# Test_2019.net
KiCad netlist of a schematic drawn in EAGLE
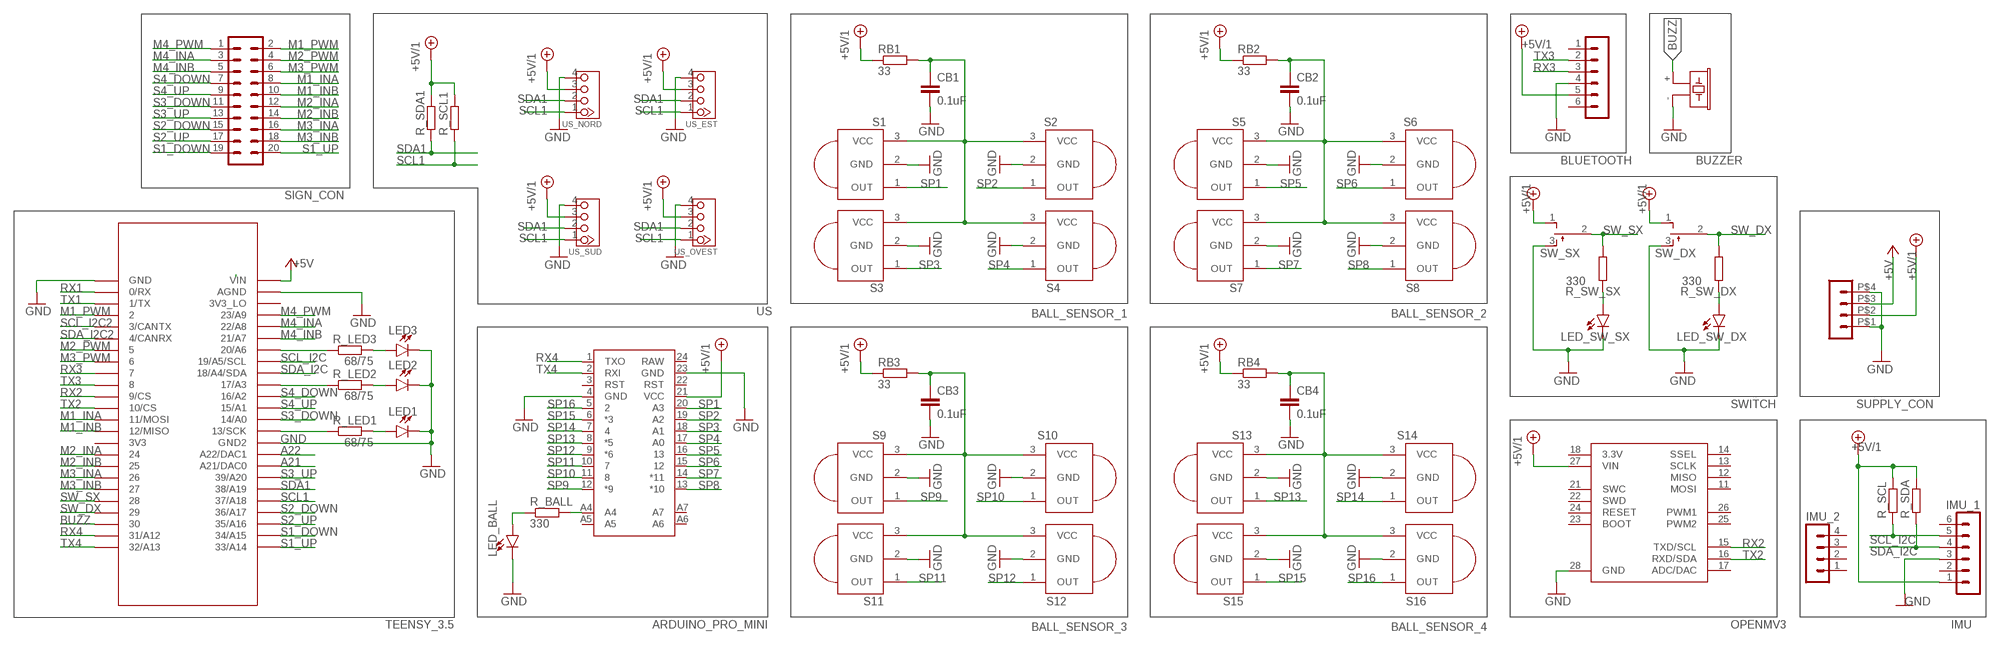
[diagram p0: schematic, sheet 1]

(export (version "E")
  (design (tool "Eeschema 10.0.6"))
  (components
    (comp (ref "ARDUINO_PRO_MINI")
      (value "ARDUINO_PRO_MINI")
      (footprint "eagle-import:ARDUINO_PRO_MINI")
      (libsource (lib "eagle-import") (part "ARDUINO_PRO_MINI"))
    )
    (comp (ref "BLUETOOTH")
      (value "MA06-1")
      (footprint "eagle-import:MA06-1")
      (libsource (lib "eagle-import") (part "MA06-1"))
    )
    (comp (ref "BUZZER")
      (value "F/CM12P")
      (footprint "eagle-import:F_CM12P")
      (libsource (lib "eagle-import") (part "F/CM12P"))
    )
    (comp (ref "CB1")
      (value "0.1uF")
      (footprint "eagle-import:C1206")
      (libsource (lib "eagle-import") (part "C-EUC1206"))
    )
    (comp (ref "CB2")
      (value "0.1uF")
      (footprint "eagle-import:C1206")
      (libsource (lib "eagle-import") (part "C-EUC1206"))
    )
    (comp (ref "CB3")
      (value "0.1uF")
      (footprint "eagle-import:C1206")
      (libsource (lib "eagle-import") (part "C-EUC1206"))
    )
    (comp (ref "CB4")
      (value "0.1uF")
      (footprint "eagle-import:C1206")
      (libsource (lib "eagle-import") (part "C-EUC1206"))
    )
    (comp (ref "IMU_1")
      (value "MA06-1")
      (footprint "eagle-import:MA06-1")
      (libsource (lib "eagle-import") (part "MA06-1"))
    )
    (comp (ref "IMU_2")
      (value "MA04-1")
      (footprint "eagle-import:MA04-1")
      (libsource (lib "eagle-import") (part "MA04-1"))
    )
    (comp (ref "LED1")
      (value "LED3MM")
      (footprint "eagle-import:LED_3MM")
      (libsource (lib "eagle-import") (part "LED3MM"))
    )
    (comp (ref "LED2")
      (value "LED3MM")
      (footprint "eagle-import:LED_3MM")
      (libsource (lib "eagle-import") (part "LED3MM"))
    )
    (comp (ref "LED3")
      (value "LED3MM")
      (footprint "eagle-import:LED_3MM")
      (libsource (lib "eagle-import") (part "LED3MM"))
    )
    (comp (ref "LED_BALL")
      (value "LED3MM")
      (footprint "eagle-import:LED_3MM")
      (libsource (lib "eagle-import") (part "LED3MM"))
    )
    (comp (ref "LED_SW_DX")
      (value "LED3MM")
      (footprint "eagle-import:LED_3MM")
      (libsource (lib "eagle-import") (part "LED3MM"))
    )
    (comp (ref "LED_SW_SX")
      (value "LED3MM")
      (footprint "eagle-import:LED_3MM")
      (libsource (lib "eagle-import") (part "LED3MM"))
    )
    (comp (ref "RB1")
      (value "33")
      (footprint "eagle-import:R0805")
      (libsource (lib "eagle-import") (part "R-EU_R0805"))
    )
    (comp (ref "RB2")
      (value "33")
      (footprint "eagle-import:R0805")
      (libsource (lib "eagle-import") (part "R-EU_R0805"))
    )
    (comp (ref "RB3")
      (value "33")
      (footprint "eagle-import:R0805")
      (libsource (lib "eagle-import") (part "R-EU_R0805"))
    )
    (comp (ref "RB4")
      (value "33")
      (footprint "eagle-import:R0805")
      (libsource (lib "eagle-import") (part "R-EU_R0805"))
    )
    (comp (ref "R_BALL")
      (value "330")
      (footprint "eagle-import:R1206")
      (libsource (lib "eagle-import") (part "R-EU_R1206"))
    )
    (comp (ref "R_LED1")
      (value "68/75")
      (footprint "eagle-import:R0805")
      (libsource (lib "eagle-import") (part "R-EU_R0805"))
    )
    (comp (ref "R_LED2")
      (value "68/75")
      (footprint "eagle-import:R0805")
      (libsource (lib "eagle-import") (part "R-EU_R0805"))
    )
    (comp (ref "R_LED3")
      (value "68/75")
      (footprint "eagle-import:R0805")
      (libsource (lib "eagle-import") (part "R-EU_R0805"))
    )
    (comp (ref "R_SCL")
      (value "3.3k")
      (footprint "eagle-import:R0805")
      (libsource (lib "eagle-import") (part "R-EU_R0805"))
    )
    (comp (ref "R_SCL1")
      (value "3.3k")
      (footprint "eagle-import:R0805")
      (libsource (lib "eagle-import") (part "R-EU_R0805"))
    )
    (comp (ref "R_SDA")
      (value "3.3k")
      (footprint "eagle-import:R0805")
      (libsource (lib "eagle-import") (part "R-EU_R0805"))
    )
    (comp (ref "R_SDA1")
      (value "3.3k")
      (footprint "eagle-import:R0805")
      (libsource (lib "eagle-import") (part "R-EU_R0805"))
    )
    (comp (ref "R_SW_DX")
      (value "330")
      (footprint "eagle-import:R0805")
      (libsource (lib "eagle-import") (part "R-EU_R0805"))
    )
    (comp (ref "R_SW_SX")
      (value "330")
      (footprint "eagle-import:R0805")
      (libsource (lib "eagle-import") (part "R-EU_R0805"))
    )
    (comp (ref "S1")
      (value "PNA460XM")
      (footprint "eagle-import:PNA460XM")
      (libsource (lib "eagle-import") (part "PNA460XM"))
    )
    (comp (ref "S2")
      (value "PNA460XM")
      (footprint "eagle-import:PNA460XM")
      (libsource (lib "eagle-import") (part "PNA460XM"))
    )
    (comp (ref "S3")
      (value "PNA460XM")
      (footprint "eagle-import:PNA460XM")
      (libsource (lib "eagle-import") (part "PNA460XM"))
    )
    (comp (ref "S4")
      (value "PNA460XM")
      (footprint "eagle-import:PNA460XM")
      (libsource (lib "eagle-import") (part "PNA460XM"))
    )
    (comp (ref "S5")
      (value "PNA460XM")
      (footprint "eagle-import:PNA460XM")
      (libsource (lib "eagle-import") (part "PNA460XM"))
    )
    (comp (ref "S6")
      (value "PNA460XM")
      (footprint "eagle-import:PNA460XM")
      (libsource (lib "eagle-import") (part "PNA460XM"))
    )
    (comp (ref "S7")
      (value "PNA460XM")
      (footprint "eagle-import:PNA460XM")
      (libsource (lib "eagle-import") (part "PNA460XM"))
    )
    (comp (ref "S8")
      (value "PNA460XM")
      (footprint "eagle-import:PNA460XM")
      (libsource (lib "eagle-import") (part "PNA460XM"))
    )
    (comp (ref "S9")
      (value "PNA460XM")
      (footprint "eagle-import:PNA460XM")
      (libsource (lib "eagle-import") (part "PNA460XM"))
    )
    (comp (ref "S10")
      (value "PNA460XM")
      (footprint "eagle-import:PNA460XM")
      (libsource (lib "eagle-import") (part "PNA460XM"))
    )
    (comp (ref "S11")
      (value "PNA460XM")
      (footprint "eagle-import:PNA460XM")
      (libsource (lib "eagle-import") (part "PNA460XM"))
    )
    (comp (ref "S12")
      (value "PNA460XM")
      (footprint "eagle-import:PNA460XM")
      (libsource (lib "eagle-import") (part "PNA460XM"))
    )
    (comp (ref "S13")
      (value "PNA460XM")
      (footprint "eagle-import:PNA460XM")
      (libsource (lib "eagle-import") (part "PNA460XM"))
    )
    (comp (ref "S14")
      (value "PNA460XM")
      (footprint "eagle-import:PNA460XM")
      (libsource (lib "eagle-import") (part "PNA460XM"))
    )
    (comp (ref "S15")
      (value "PNA460XM")
      (footprint "eagle-import:PNA460XM")
      (libsource (lib "eagle-import") (part "PNA460XM"))
    )
    (comp (ref "S16")
      (value "PNA460XM")
      (footprint "eagle-import:PNA460XM")
      (libsource (lib "eagle-import") (part "PNA460XM"))
    )
    (comp (ref "SIGN_CON")
      (value "20V")
      (footprint "eagle-import:20V")
      (libsource (lib "eagle-import") (part "20V"))
    )
    (comp (ref "SUPPLY_CON")
      (value "HEADER_POS4_43045-0412")
      (footprint "eagle-import:43045-0412")
      (libsource (lib "eagle-import") (part "HEADER_POS4_?43045-0412"))
    )
    (comp (ref "SW_DX")
      (value "TL38PO")
      (footprint "eagle-import:TL3XPO")
      (libsource (lib "eagle-import") (part "TL38PO"))
    )
    (comp (ref "SW_SX")
      (value "TL38PO")
      (footprint "eagle-import:TL3XPO")
      (libsource (lib "eagle-import") (part "TL38PO"))
    )
    (comp (ref "TEENSY_3.5")
      (value "TEENSY_3.5/3.6")
      (footprint "eagle-import:TEENSY_3.5_3.6")
      (libsource (lib "eagle-import") (part "TEENSY_3.5/3.6"))
    )
    (comp (ref "U$2")
      (value "OPENMV3")
      (footprint "eagle-import:OPENMV3")
      (libsource (lib "eagle-import") (part "OPENMV3"))
    )
    (comp (ref "US_EST")
      (value "TWIG_2.0")
      (footprint "eagle-import:2.0_1X4")
      (libsource (lib "eagle-import") (part "TWIG_2.0"))
    )
    (comp (ref "US_NORD")
      (value "TWIG_2.0")
      (footprint "eagle-import:2.0_1X4")
      (libsource (lib "eagle-import") (part "TWIG_2.0"))
    )
    (comp (ref "US_OVEST")
      (value "TWIG_2.0")
      (footprint "eagle-import:2.0_1X4")
      (libsource (lib "eagle-import") (part "TWIG_2.0"))
    )
    (comp (ref "US_SUD")
      (value "TWIG_2.0")
      (footprint "eagle-import:2.0_1X4")
      (libsource (lib "eagle-import") (part "TWIG_2.0"))
    )
  )
  (nets
    (net (code "1") (name "+5V") (class "Default")
      (node (ref "SUPPLY_CON") (pin "P$3") (pinfunction "3_P$3") (pintype "passive"))
      (node (ref "TEENSY_3.5") (pin "VIN") (pinfunction "VIN_VIN") (pintype "bidirectional"))
    )
    (net (code "2") (name "+5V{slash}1") (class "Default")
      (node (ref "ARDUINO_PRO_MINI") (pin "21") (pinfunction "VCC_21") (pintype "power_in"))
      (node (ref "BLUETOOTH") (pin "5") (pinfunction "5_5") (pintype "passive"))
      (node (ref "IMU_1") (pin "1") (pinfunction "1_1") (pintype "passive"))
      (node (ref "RB1") (pin "1") (pinfunction "1_1") (pintype "passive"))
      (node (ref "RB2") (pin "1") (pinfunction "1_1") (pintype "passive"))
      (node (ref "RB3") (pin "1") (pinfunction "1_1") (pintype "passive"))
      (node (ref "RB4") (pin "1") (pinfunction "1_1") (pintype "passive"))
      (node (ref "R_SCL") (pin "2") (pinfunction "2_2") (pintype "passive"))
      (node (ref "R_SCL1") (pin "2") (pinfunction "2_2") (pintype "passive"))
      (node (ref "R_SDA") (pin "2") (pinfunction "2_2") (pintype "passive"))
      (node (ref "R_SDA1") (pin "2") (pinfunction "2_2") (pintype "passive"))
      (node (ref "SUPPLY_CON") (pin "P$2") (pinfunction "2_P$2") (pintype "passive"))
      (node (ref "SW_DX") (pin "1") (pinfunction "O_1") (pintype "passive"))
      (node (ref "SW_SX") (pin "1") (pinfunction "O_1") (pintype "passive"))
      (node (ref "U$2") (pin "27") (pinfunction "VIN_27") (pintype "power_in"))
      (node (ref "US_EST") (pin "3") (pinfunction "3_3") (pintype "bidirectional"))
      (node (ref "US_NORD") (pin "3") (pinfunction "3_3") (pintype "bidirectional"))
      (node (ref "US_OVEST") (pin "3") (pinfunction "3_3") (pintype "bidirectional"))
      (node (ref "US_SUD") (pin "3") (pinfunction "3_3") (pintype "bidirectional"))
    )
    (net (code "3") (name "/3.3V") (class "Default")
      (node (ref "U$2") (pin "18") (pinfunction "3.3V_18") (pintype "power_in"))
    )
    (net (code "4") (name "/A21") (class "Default")
      (node (ref "TEENSY_3.5") (pin "21/DAC0") (pinfunction "A21/DAC0_21/DAC0") (pintype "bidirectional"))
    )
    (net (code "5") (name "/A22") (class "Default")
      (node (ref "TEENSY_3.5") (pin "A22/DAC1") (pinfunction "A22/DAC1_A22/DAC1") (pintype "bidirectional"))
    )
    (net (code "6") (name "/M1_INA") (class "Default")
      (node (ref "SIGN_CON") (pin "8") (pinfunction "8_8") (pintype "passive"))
      (node (ref "TEENSY_3.5") (pin "11/MOSI") (pinfunction "11/MOSI_11/MOSI") (pintype "bidirectional"))
    )
    (net (code "7") (name "/M1_INB") (class "Default")
      (node (ref "SIGN_CON") (pin "10") (pinfunction "10_10") (pintype "passive"))
      (node (ref "TEENSY_3.5") (pin "12/MISO") (pinfunction "12/MISO_12/MISO") (pintype "bidirectional"))
    )
    (net (code "8") (name "/M1_PWM") (class "Default")
      (node (ref "SIGN_CON") (pin "2") (pinfunction "2_2") (pintype "passive"))
      (node (ref "TEENSY_3.5") (pin "2") (pinfunction "2_2") (pintype "bidirectional"))
    )
    (net (code "9") (name "/M2_INA") (class "Default")
      (node (ref "SIGN_CON") (pin "12") (pinfunction "12_12") (pintype "passive"))
      (node (ref "TEENSY_3.5") (pin "24") (pinfunction "24_24") (pintype "bidirectional"))
    )
    (net (code "10") (name "/M2_INB") (class "Default")
      (node (ref "SIGN_CON") (pin "14") (pinfunction "14_14") (pintype "passive"))
      (node (ref "TEENSY_3.5") (pin "25") (pinfunction "25_25") (pintype "bidirectional"))
    )
    (net (code "11") (name "/M2_PWM") (class "Default")
      (node (ref "SIGN_CON") (pin "4") (pinfunction "4_4") (pintype "passive"))
      (node (ref "TEENSY_3.5") (pin "5") (pinfunction "5_5") (pintype "bidirectional"))
    )
    (net (code "12") (name "/M3_INA") (class "Default")
      (node (ref "SIGN_CON") (pin "16") (pinfunction "16_16") (pintype "passive"))
      (node (ref "TEENSY_3.5") (pin "26") (pinfunction "26_26") (pintype "bidirectional"))
    )
    (net (code "13") (name "/M3_INB") (class "Default")
      (node (ref "SIGN_CON") (pin "18") (pinfunction "18_18") (pintype "passive"))
      (node (ref "TEENSY_3.5") (pin "27") (pinfunction "27_27") (pintype "bidirectional"))
    )
    (net (code "14") (name "/M3_PWM") (class "Default")
      (node (ref "SIGN_CON") (pin "6") (pinfunction "6_6") (pintype "passive"))
      (node (ref "TEENSY_3.5") (pin "6") (pinfunction "6_6") (pintype "bidirectional"))
    )
    (net (code "15") (name "/M4_INA") (class "Default")
      (node (ref "SIGN_CON") (pin "3") (pinfunction "3_3") (pintype "passive"))
      (node (ref "TEENSY_3.5") (pin "22/A8") (pinfunction "22/A8_22/A8") (pintype "bidirectional"))
    )
    (net (code "16") (name "/M4_INB") (class "Default")
      (node (ref "SIGN_CON") (pin "5") (pinfunction "5_5") (pintype "passive"))
      (node (ref "TEENSY_3.5") (pin "21/A7") (pinfunction "21/A7_21/A7") (pintype "bidirectional"))
    )
    (net (code "17") (name "/M4_PWM") (class "Default")
      (node (ref "SIGN_CON") (pin "1") (pinfunction "1_1") (pintype "passive"))
      (node (ref "TEENSY_3.5") (pin "23/A9") (pinfunction "23/A9_23/A9") (pintype "bidirectional"))
    )
    (net (code "18") (name "/RAW") (class "Default")
      (node (ref "ARDUINO_PRO_MINI") (pin "24") (pinfunction "RAW_24") (pintype "power_in"))
    )
    (net (code "19") (name "/RX1") (class "Default")
      (node (ref "TEENSY_3.5") (pin "0/RX") (pinfunction "0/RX_0/RX") (pintype "bidirectional"))
    )
    (net (code "20") (name "/RX2") (class "Default")
      (node (ref "TEENSY_3.5") (pin "9/CS") (pinfunction "9/CS_9/CS") (pintype "bidirectional"))
      (node (ref "U$2") (pin "15") (pinfunction "TXD/SCL_15") (pintype "bidirectional"))
    )
    (net (code "21") (name "/RX3") (class "Default")
      (node (ref "BLUETOOTH") (pin "3") (pinfunction "3_3") (pintype "passive"))
      (node (ref "TEENSY_3.5") (pin "7") (pinfunction "7_7") (pintype "bidirectional"))
    )
    (net (code "22") (name "/RX4") (class "Default")
      (node (ref "ARDUINO_PRO_MINI") (pin "1") (pinfunction "TXO_1") (pintype "bidirectional"))
      (node (ref "TEENSY_3.5") (pin "31/A12") (pinfunction "31/A12_31/A12") (pintype "bidirectional"))
    )
    (net (code "23") (name "/S1_DOWN") (class "Default")
      (node (ref "SIGN_CON") (pin "19") (pinfunction "19_19") (pintype "passive"))
      (node (ref "TEENSY_3.5") (pin "34/A15") (pinfunction "34/A15_34/A15") (pintype "bidirectional"))
    )
    (net (code "24") (name "/S1_UP") (class "Default")
      (node (ref "SIGN_CON") (pin "20") (pinfunction "20_20") (pintype "passive"))
      (node (ref "TEENSY_3.5") (pin "33/A14") (pinfunction "33/A14_33/A14") (pintype "bidirectional"))
    )
    (net (code "25") (name "/S2_DOWN") (class "Default")
      (node (ref "SIGN_CON") (pin "15") (pinfunction "15_15") (pintype "passive"))
      (node (ref "TEENSY_3.5") (pin "36/A17") (pinfunction "36/A17_36/A17") (pintype "bidirectional"))
    )
    (net (code "26") (name "/S2_UP") (class "Default")
      (node (ref "SIGN_CON") (pin "17") (pinfunction "17_17") (pintype "passive"))
      (node (ref "TEENSY_3.5") (pin "35/A16") (pinfunction "35/A16_35/A16") (pintype "bidirectional"))
    )
    (net (code "27") (name "/S3_DOWN") (class "Default")
      (node (ref "SIGN_CON") (pin "11") (pinfunction "11_11") (pintype "passive"))
      (node (ref "TEENSY_3.5") (pin "14/A0") (pinfunction "14/A0_14/A0") (pintype "bidirectional"))
    )
    (net (code "28") (name "/S3_UP") (class "Default")
      (node (ref "SIGN_CON") (pin "13") (pinfunction "13_13") (pintype "passive"))
      (node (ref "TEENSY_3.5") (pin "39/A20") (pinfunction "39/A20_39/A20") (pintype "bidirectional"))
    )
    (net (code "29") (name "/S4_DOWN") (class "Default")
      (node (ref "SIGN_CON") (pin "7") (pinfunction "7_7") (pintype "passive"))
      (node (ref "TEENSY_3.5") (pin "16/A2") (pinfunction "16/A2_16/A2") (pintype "bidirectional"))
    )
    (net (code "30") (name "/S4_UP") (class "Default")
      (node (ref "SIGN_CON") (pin "9") (pinfunction "9_9") (pintype "passive"))
      (node (ref "TEENSY_3.5") (pin "15/A1") (pinfunction "15/A1_15/A1") (pintype "bidirectional"))
    )
    (net (code "31") (name "/SCL1") (class "Default")
      (node (ref "R_SCL1") (pin "1") (pinfunction "1_1") (pintype "passive"))
      (node (ref "TEENSY_3.5") (pin "37/A18") (pinfunction "37/A18_37/A18") (pintype "bidirectional"))
      (node (ref "US_EST") (pin "1") (pinfunction "1_1") (pintype "bidirectional"))
      (node (ref "US_NORD") (pin "1") (pinfunction "1_1") (pintype "bidirectional"))
      (node (ref "US_OVEST") (pin "1") (pinfunction "1_1") (pintype "bidirectional"))
      (node (ref "US_SUD") (pin "1") (pinfunction "1_1") (pintype "bidirectional"))
    )
    (net (code "32") (name "/SCL_I2C") (class "Default")
      (node (ref "IMU_1") (pin "5") (pinfunction "5_5") (pintype "passive"))
      (node (ref "R_SCL") (pin "1") (pinfunction "1_1") (pintype "passive"))
      (node (ref "TEENSY_3.5") (pin "19/A5/SCL") (pinfunction "19/A5/SCL_19/A5/SCL") (pintype "bidirectional"))
    )
    (net (code "33") (name "/SCL_I2C2") (class "Default")
      (node (ref "TEENSY_3.5") (pin "3/CANTX") (pinfunction "3/CANTX_3/CANTX") (pintype "bidirectional"))
    )
    (net (code "34") (name "/SDA1") (class "Default")
      (node (ref "R_SDA1") (pin "1") (pinfunction "1_1") (pintype "passive"))
      (node (ref "TEENSY_3.5") (pin "38/A19") (pinfunction "38/A19_38/A19") (pintype "bidirectional"))
      (node (ref "US_EST") (pin "2") (pinfunction "2_2") (pintype "bidirectional"))
      (node (ref "US_NORD") (pin "2") (pinfunction "2_2") (pintype "bidirectional"))
      (node (ref "US_OVEST") (pin "2") (pinfunction "2_2") (pintype "bidirectional"))
      (node (ref "US_SUD") (pin "2") (pinfunction "2_2") (pintype "bidirectional"))
    )
    (net (code "35") (name "/SDA_I2C") (class "Default")
      (node (ref "IMU_1") (pin "4") (pinfunction "4_4") (pintype "passive"))
      (node (ref "R_SDA") (pin "1") (pinfunction "1_1") (pintype "passive"))
      (node (ref "TEENSY_3.5") (pin "18/A4/SDA") (pinfunction "18/A4/SDA_18/A4/SDA") (pintype "bidirectional"))
    )
    (net (code "36") (name "/SDA_I2C2") (class "Default")
      (node (ref "TEENSY_3.5") (pin "4/CANRX") (pinfunction "4/CANRX_4/CANRX") (pintype "bidirectional"))
    )
    (net (code "37") (name "/SP1") (class "Default")
      (node (ref "ARDUINO_PRO_MINI") (pin "20") (pinfunction "A3_20") (pintype "bidirectional"))
      (node (ref "S1") (pin "1") (pinfunction "OUT_1") (pintype "output"))
    )
    (net (code "38") (name "/SP2") (class "Default")
      (node (ref "ARDUINO_PRO_MINI") (pin "19") (pinfunction "A2_19") (pintype "bidirectional"))
      (node (ref "S2") (pin "1") (pinfunction "OUT_1") (pintype "output"))
    )
    (net (code "39") (name "/SP3") (class "Default")
      (node (ref "ARDUINO_PRO_MINI") (pin "18") (pinfunction "A1_18") (pintype "bidirectional"))
      (node (ref "S3") (pin "1") (pinfunction "OUT_1") (pintype "output"))
    )
    (net (code "40") (name "/SP4") (class "Default")
      (node (ref "ARDUINO_PRO_MINI") (pin "17") (pinfunction "A0_17") (pintype "bidirectional"))
      (node (ref "S4") (pin "1") (pinfunction "OUT_1") (pintype "output"))
    )
    (net (code "41") (name "/SP5") (class "Default")
      (node (ref "ARDUINO_PRO_MINI") (pin "16") (pinfunction "13_16") (pintype "bidirectional"))
      (node (ref "S5") (pin "1") (pinfunction "OUT_1") (pintype "output"))
    )
    (net (code "42") (name "/SP6") (class "Default")
      (node (ref "ARDUINO_PRO_MINI") (pin "15") (pinfunction "12_15") (pintype "bidirectional"))
      (node (ref "S6") (pin "1") (pinfunction "OUT_1") (pintype "output"))
    )
    (net (code "43") (name "/SP7") (class "Default")
      (node (ref "ARDUINO_PRO_MINI") (pin "14") (pinfunction "*11_14") (pintype "bidirectional"))
      (node (ref "S7") (pin "1") (pinfunction "OUT_1") (pintype "output"))
    )
    (net (code "44") (name "/SP8") (class "Default")
      (node (ref "ARDUINO_PRO_MINI") (pin "13") (pinfunction "*10_13") (pintype "bidirectional"))
      (node (ref "S8") (pin "1") (pinfunction "OUT_1") (pintype "output"))
    )
    (net (code "45") (name "/SP9") (class "Default")
      (node (ref "ARDUINO_PRO_MINI") (pin "12") (pinfunction "*9_12") (pintype "bidirectional"))
      (node (ref "S9") (pin "1") (pinfunction "OUT_1") (pintype "output"))
    )
    (net (code "46") (name "/SP10") (class "Default")
      (node (ref "ARDUINO_PRO_MINI") (pin "11") (pinfunction "8_11") (pintype "bidirectional"))
      (node (ref "S10") (pin "1") (pinfunction "OUT_1") (pintype "output"))
    )
    (net (code "47") (name "/SP11") (class "Default")
      (node (ref "ARDUINO_PRO_MINI") (pin "10") (pinfunction "7_10") (pintype "bidirectional"))
      (node (ref "S11") (pin "1") (pinfunction "OUT_1") (pintype "output"))
    )
    (net (code "48") (name "/SP12") (class "Default")
      (node (ref "ARDUINO_PRO_MINI") (pin "9") (pinfunction "*6_9") (pintype "bidirectional"))
      (node (ref "S12") (pin "1") (pinfunction "OUT_1") (pintype "output"))
    )
    (net (code "49") (name "/SP13") (class "Default")
      (node (ref "ARDUINO_PRO_MINI") (pin "8") (pinfunction "*5_8") (pintype "bidirectional"))
      (node (ref "S13") (pin "1") (pinfunction "OUT_1") (pintype "output"))
    )
    (net (code "50") (name "/SP14") (class "Default")
      (node (ref "ARDUINO_PRO_MINI") (pin "7") (pinfunction "4_7") (pintype "bidirectional"))
      (node (ref "S14") (pin "1") (pinfunction "OUT_1") (pintype "output"))
    )
    (net (code "51") (name "/SP15") (class "Default")
      (node (ref "ARDUINO_PRO_MINI") (pin "6") (pinfunction "*3_6") (pintype "bidirectional"))
      (node (ref "S15") (pin "1") (pinfunction "OUT_1") (pintype "output"))
    )
    (net (code "52") (name "/SP16") (class "Default")
      (node (ref "ARDUINO_PRO_MINI") (pin "5") (pinfunction "2_5") (pintype "bidirectional"))
      (node (ref "S16") (pin "1") (pinfunction "OUT_1") (pintype "output"))
    )
    (net (code "53") (name "/SW_DX") (class "Default")
      (node (ref "R_SW_DX") (pin "2") (pinfunction "2_2") (pintype "passive"))
      (node (ref "SW_DX") (pin "2") (pinfunction "P_2") (pintype "passive"))
      (node (ref "TEENSY_3.5") (pin "29") (pinfunction "29_29") (pintype "bidirectional"))
    )
    (net (code "54") (name "/SW_SX") (class "Default")
      (node (ref "R_SW_SX") (pin "2") (pinfunction "2_2") (pintype "passive"))
      (node (ref "SW_SX") (pin "2") (pinfunction "P_2") (pintype "passive"))
      (node (ref "TEENSY_3.5") (pin "28") (pinfunction "28_28") (pintype "bidirectional"))
    )
    (net (code "55") (name "/TX1") (class "Default")
      (node (ref "TEENSY_3.5") (pin "1/TX") (pinfunction "1/TX_1/TX") (pintype "bidirectional"))
    )
    (net (code "56") (name "/TX2") (class "Default")
      (node (ref "TEENSY_3.5") (pin "10/CS") (pinfunction "10/CS_10/CS") (pintype "bidirectional"))
      (node (ref "U$2") (pin "16") (pinfunction "RXD/SDA_16") (pintype "bidirectional"))
    )
    (net (code "57") (name "/TX3") (class "Default")
      (node (ref "BLUETOOTH") (pin "2") (pinfunction "2_2") (pintype "passive"))
      (node (ref "TEENSY_3.5") (pin "8") (pinfunction "8_8") (pintype "bidirectional"))
    )
    (net (code "58") (name "/TX4") (class "Default")
      (node (ref "ARDUINO_PRO_MINI") (pin "2") (pinfunction "RXI_2") (pintype "bidirectional"))
      (node (ref "TEENSY_3.5") (pin "32/A13") (pinfunction "32/A13_32/A13") (pintype "bidirectional"))
    )
    (net (code "59") (name "BUZZ") (class "Default")
      (node (ref "BUZZER") (pin "+") (pinfunction "1_+") (pintype "passive"))
      (node (ref "TEENSY_3.5") (pin "30") (pinfunction "30_30") (pintype "bidirectional"))
    )
    (net (code "60") (name "GND") (class "Default")
      (node (ref "ARDUINO_PRO_MINI") (pin "23") (pinfunction "GND_23") (pintype "power_in"))
      (node (ref "ARDUINO_PRO_MINI") (pin "4") (pinfunction "GND_4") (pintype "power_in"))
      (node (ref "BLUETOOTH") (pin "4") (pinfunction "4_4") (pintype "passive"))
      (node (ref "BUZZER") (pin "-") (pinfunction "2_-") (pintype "passive"))
      (node (ref "CB1") (pin "2") (pinfunction "2_2") (pintype "passive"))
      (node (ref "CB2") (pin "2") (pinfunction "2_2") (pintype "passive"))
      (node (ref "CB3") (pin "2") (pinfunction "2_2") (pintype "passive"))
      (node (ref "CB4") (pin "2") (pinfunction "2_2") (pintype "passive"))
      (node (ref "IMU_1") (pin "3") (pinfunction "3_3") (pintype "passive"))
      (node (ref "LED1") (pin "K") (pinfunction "C_K") (pintype "passive"))
      (node (ref "LED2") (pin "K") (pinfunction "C_K") (pintype "passive"))
      (node (ref "LED3") (pin "K") (pinfunction "C_K") (pintype "passive"))
      (node (ref "LED_BALL") (pin "K") (pinfunction "C_K") (pintype "passive"))
      (node (ref "LED_SW_DX") (pin "K") (pinfunction "C_K") (pintype "passive"))
      (node (ref "LED_SW_SX") (pin "K") (pinfunction "C_K") (pintype "passive"))
      (node (ref "S1") (pin "2") (pinfunction "GND_2") (pintype "power_in"))
      (node (ref "S10") (pin "2") (pinfunction "GND_2") (pintype "power_in"))
      (node (ref "S11") (pin "2") (pinfunction "GND_2") (pintype "power_in"))
      (node (ref "S12") (pin "2") (pinfunction "GND_2") (pintype "power_in"))
      (node (ref "S13") (pin "2") (pinfunction "GND_2") (pintype "power_in"))
      (node (ref "S14") (pin "2") (pinfunction "GND_2") (pintype "power_in"))
      (node (ref "S15") (pin "2") (pinfunction "GND_2") (pintype "power_in"))
      (node (ref "S16") (pin "2") (pinfunction "GND_2") (pintype "power_in"))
      (node (ref "S2") (pin "2") (pinfunction "GND_2") (pintype "power_in"))
      (node (ref "S3") (pin "2") (pinfunction "GND_2") (pintype "power_in"))
      (node (ref "S4") (pin "2") (pinfunction "GND_2") (pintype "power_in"))
      (node (ref "S5") (pin "2") (pinfunction "GND_2") (pintype "power_in"))
      (node (ref "S6") (pin "2") (pinfunction "GND_2") (pintype "power_in"))
      (node (ref "S7") (pin "2") (pinfunction "GND_2") (pintype "power_in"))
      (node (ref "S8") (pin "2") (pinfunction "GND_2") (pintype "power_in"))
      (node (ref "S9") (pin "2") (pinfunction "GND_2") (pintype "power_in"))
      (node (ref "SUPPLY_CON") (pin "P$1") (pinfunction "1_P$1") (pintype "passive"))
      (node (ref "SUPPLY_CON") (pin "P$4") (pinfunction "4_P$4") (pintype "passive"))
      (node (ref "SW_DX") (pin "3") (pinfunction "S_3") (pintype "passive"))
      (node (ref "SW_SX") (pin "3") (pinfunction "S_3") (pintype "passive"))
      (node (ref "TEENSY_3.5") (pin "AGND") (pinfunction "AGND_AGND") (pintype "bidirectional"))
      (node (ref "TEENSY_3.5") (pin "GND") (pinfunction "GND_GND") (pintype "bidirectional"))
      (node (ref "TEENSY_3.5") (pin "GND2") (pinfunction "GND2_GND2") (pintype "bidirectional"))
      (node (ref "U$2") (pin "28") (pinfunction "GND_28") (pintype "power_in"))
      (node (ref "US_EST") (pin "4") (pinfunction "4_4") (pintype "bidirectional"))
      (node (ref "US_NORD") (pin "4") (pinfunction "4_4") (pintype "bidirectional"))
      (node (ref "US_OVEST") (pin "4") (pinfunction "4_4") (pintype "bidirectional"))
      (node (ref "US_SUD") (pin "4") (pinfunction "4_4") (pintype "bidirectional"))
    )
    (net (code "61") (name "Net-(ARDUINO_PRO_MINI-PadA4)") (class "Default")
      (node (ref "ARDUINO_PRO_MINI") (pin "A4") (pinfunction "A4_A4") (pintype "bidirectional"))
      (node (ref "R_BALL") (pin "2") (pinfunction "2_2") (pintype "passive"))
    )
    (net (code "62") (name "Net-(LED1-PadA)") (class "Default")
      (node (ref "LED1") (pin "A") (pinfunction "A_A") (pintype "passive"))
      (node (ref "R_LED1") (pin "2") (pinfunction "2_2") (pintype "passive"))
    )
    (net (code "63") (name "Net-(LED2-PadA)") (class "Default")
      (node (ref "LED2") (pin "A") (pinfunction "A_A") (pintype "passive"))
      (node (ref "R_LED2") (pin "2") (pinfunction "2_2") (pintype "passive"))
    )
    (net (code "64") (name "Net-(LED3-PadA)") (class "Default")
      (node (ref "LED3") (pin "A") (pinfunction "A_A") (pintype "passive"))
      (node (ref "R_LED3") (pin "2") (pinfunction "2_2") (pintype "passive"))
    )
    (net (code "65") (name "Net-(LED_BALL-PadA)") (class "Default")
      (node (ref "LED_BALL") (pin "A") (pinfunction "A_A") (pintype "passive"))
      (node (ref "R_BALL") (pin "1") (pinfunction "1_1") (pintype "passive"))
    )
    (net (code "66") (name "Net-(LED_SW_DX-PadA)") (class "Default")
      (node (ref "LED_SW_DX") (pin "A") (pinfunction "A_A") (pintype "passive"))
      (node (ref "R_SW_DX") (pin "1") (pinfunction "1_1") (pintype "passive"))
    )
    (net (code "67") (name "Net-(LED_SW_SX-PadA)") (class "Default")
      (node (ref "LED_SW_SX") (pin "A") (pinfunction "A_A") (pintype "passive"))
      (node (ref "R_SW_SX") (pin "1") (pinfunction "1_1") (pintype "passive"))
    )
    (net (code "68") (name "Net-(R_LED1-Pad1)") (class "Default")
      (node (ref "R_LED1") (pin "1") (pinfunction "1_1") (pintype "passive"))
      (node (ref "TEENSY_3.5") (pin "13/SCK") (pinfunction "13/SCK_13/SCK") (pintype "bidirectional"))
    )
    (net (code "69") (name "Net-(R_LED2-Pad1)") (class "Default")
      (node (ref "R_LED2") (pin "1") (pinfunction "1_1") (pintype "passive"))
      (node (ref "TEENSY_3.5") (pin "17/A3") (pinfunction "17/A3_17/A3") (pintype "bidirectional"))
    )
    (net (code "70") (name "Net-(R_LED3-Pad1)") (class "Default")
      (node (ref "R_LED3") (pin "1") (pinfunction "1_1") (pintype "passive"))
      (node (ref "TEENSY_3.5") (pin "20/A6") (pinfunction "20/A6_20/A6") (pintype "bidirectional"))
    )
    (net (code "71") (name "Net-(S1-VCC)") (class "Default")
      (node (ref "CB1") (pin "1") (pinfunction "1_1") (pintype "passive"))
      (node (ref "RB1") (pin "2") (pinfunction "2_2") (pintype "passive"))
      (node (ref "S1") (pin "3") (pinfunction "VCC_3") (pintype "power_in"))
      (node (ref "S2") (pin "3") (pinfunction "VCC_3") (pintype "power_in"))
      (node (ref "S3") (pin "3") (pinfunction "VCC_3") (pintype "power_in"))
      (node (ref "S4") (pin "3") (pinfunction "VCC_3") (pintype "power_in"))
    )
    (net (code "72") (name "Net-(S5-VCC)") (class "Default")
      (node (ref "CB2") (pin "1") (pinfunction "1_1") (pintype "passive"))
      (node (ref "RB2") (pin "2") (pinfunction "2_2") (pintype "passive"))
      (node (ref "S5") (pin "3") (pinfunction "VCC_3") (pintype "power_in"))
      (node (ref "S6") (pin "3") (pinfunction "VCC_3") (pintype "power_in"))
      (node (ref "S7") (pin "3") (pinfunction "VCC_3") (pintype "power_in"))
      (node (ref "S8") (pin "3") (pinfunction "VCC_3") (pintype "power_in"))
    )
    (net (code "73") (name "Net-(S10-VCC)") (class "Default")
      (node (ref "CB3") (pin "1") (pinfunction "1_1") (pintype "passive"))
      (node (ref "RB3") (pin "2") (pinfunction "2_2") (pintype "passive"))
      (node (ref "S10") (pin "3") (pinfunction "VCC_3") (pintype "power_in"))
      (node (ref "S11") (pin "3") (pinfunction "VCC_3") (pintype "power_in"))
      (node (ref "S12") (pin "3") (pinfunction "VCC_3") (pintype "power_in"))
      (node (ref "S9") (pin "3") (pinfunction "VCC_3") (pintype "power_in"))
    )
    (net (code "74") (name "Net-(S13-VCC)") (class "Default")
      (node (ref "CB4") (pin "1") (pinfunction "1_1") (pintype "passive"))
      (node (ref "RB4") (pin "2") (pinfunction "2_2") (pintype "passive"))
      (node (ref "S13") (pin "3") (pinfunction "VCC_3") (pintype "power_in"))
      (node (ref "S14") (pin "3") (pinfunction "VCC_3") (pintype "power_in"))
      (node (ref "S15") (pin "3") (pinfunction "VCC_3") (pintype "power_in"))
      (node (ref "S16") (pin "3") (pinfunction "VCC_3") (pintype "power_in"))
    )
    (net (code "75") (name "unconnected-(ARDUINO_PRO_MINI-PadA5)") (class "Default")
      (node (ref "ARDUINO_PRO_MINI") (pin "A5") (pinfunction "A5_A5") (pintype "bidirectional"))
    )
    (net (code "76") (name "unconnected-(ARDUINO_PRO_MINI-PadA6)") (class "Default")
      (node (ref "ARDUINO_PRO_MINI") (pin "A6") (pinfunction "A6_A6") (pintype "bidirectional"))
    )
    (net (code "77") (name "unconnected-(ARDUINO_PRO_MINI-PadA7)") (class "Default")
      (node (ref "ARDUINO_PRO_MINI") (pin "A7") (pinfunction "A7_A7") (pintype "bidirectional"))
    )
    (net (code "78") (name "unconnected-(ARDUINO_PRO_MINI-RST-Pad3)") (class "Default")
      (node (ref "ARDUINO_PRO_MINI") (pin "3") (pinfunction "RST_3") (pintype "bidirectional"))
    )
    (net (code "79") (name "unconnected-(ARDUINO_PRO_MINI-RST-Pad22)") (class "Default")
      (node (ref "ARDUINO_PRO_MINI") (pin "22") (pinfunction "RST_22") (pintype "bidirectional"))
    )
    (net (code "80") (name "unconnected-(BLUETOOTH-Pad1)") (class "Default")
      (node (ref "BLUETOOTH") (pin "1") (pinfunction "1_1") (pintype "passive"))
    )
    (net (code "81") (name "unconnected-(BLUETOOTH-Pad6)") (class "Default")
      (node (ref "BLUETOOTH") (pin "6") (pinfunction "6_6") (pintype "passive"))
    )
    (net (code "82") (name "unconnected-(IMU_1-Pad2)") (class "Default")
      (node (ref "IMU_1") (pin "2") (pinfunction "2_2") (pintype "passive"))
    )
    (net (code "83") (name "unconnected-(IMU_1-Pad6)") (class "Default")
      (node (ref "IMU_1") (pin "6") (pinfunction "6_6") (pintype "passive"))
    )
    (net (code "84") (name "unconnected-(IMU_2-Pad1)") (class "Default")
      (node (ref "IMU_2") (pin "1") (pinfunction "1_1") (pintype "passive"))
    )
    (net (code "85") (name "unconnected-(IMU_2-Pad2)") (class "Default")
      (node (ref "IMU_2") (pin "2") (pinfunction "2_2") (pintype "passive"))
    )
    (net (code "86") (name "unconnected-(IMU_2-Pad3)") (class "Default")
      (node (ref "IMU_2") (pin "3") (pinfunction "3_3") (pintype "passive"))
    )
    (net (code "87") (name "unconnected-(IMU_2-Pad4)") (class "Default")
      (node (ref "IMU_2") (pin "4") (pinfunction "4_4") (pintype "passive"))
    )
    (net (code "88") (name "unconnected-(TEENSY_3.5-Pad3V3)") (class "Default")
      (node (ref "TEENSY_3.5") (pin "3V3") (pinfunction "3V3_3V3") (pintype "bidirectional"))
    )
    (net (code "89") (name "unconnected-(TEENSY_3.5-Pad3V3_LO)") (class "Default")
      (node (ref "TEENSY_3.5") (pin "3V3_LO") (pinfunction "3V3_LO_3V3_LO") (pintype "bidirectional"))
    )
    (net (code "90") (name "unconnected-(U$2-ADC{slash}DAC-Pad17)") (class "Default")
      (node (ref "U$2") (pin "17") (pinfunction "ADC/DAC_17") (pintype "bidirectional"))
    )
    (net (code "91") (name "unconnected-(U$2-BOOT-Pad23)") (class "Default")
      (node (ref "U$2") (pin "23") (pinfunction "BOOT_23") (pintype "bidirectional"))
    )
    (net (code "92") (name "unconnected-(U$2-MISO-Pad12)") (class "Default")
      (node (ref "U$2") (pin "12") (pinfunction "MISO_12") (pintype "bidirectional"))
    )
    (net (code "93") (name "unconnected-(U$2-MOSI-Pad11)") (class "Default")
      (node (ref "U$2") (pin "11") (pinfunction "MOSI_11") (pintype "bidirectional"))
    )
    (net (code "94") (name "unconnected-(U$2-PWM1-Pad26)") (class "Default")
      (node (ref "U$2") (pin "26") (pinfunction "PWM1_26") (pintype "bidirectional"))
    )
    (net (code "95") (name "unconnected-(U$2-PWM2-Pad25)") (class "Default")
      (node (ref "U$2") (pin "25") (pinfunction "PWM2_25") (pintype "bidirectional"))
    )
    (net (code "96") (name "unconnected-(U$2-RESET-Pad24)") (class "Default")
      (node (ref "U$2") (pin "24") (pinfunction "RESET_24") (pintype "bidirectional"))
    )
    (net (code "97") (name "unconnected-(U$2-SCLK-Pad13)") (class "Default")
      (node (ref "U$2") (pin "13") (pinfunction "SCLK_13") (pintype "bidirectional"))
    )
    (net (code "98") (name "unconnected-(U$2-SSEL-Pad14)") (class "Default")
      (node (ref "U$2") (pin "14") (pinfunction "SSEL_14") (pintype "bidirectional"))
    )
    (net (code "99") (name "unconnected-(U$2-SWC-Pad21)") (class "Default")
      (node (ref "U$2") (pin "21") (pinfunction "SWC_21") (pintype "bidirectional"))
    )
    (net (code "100") (name "unconnected-(U$2-SWD-Pad22)") (class "Default")
      (node (ref "U$2") (pin "22") (pinfunction "SWD_22") (pintype "bidirectional"))
    )
  )
)
